# MCU_old.net
KiCad netlist of a schematic drawn in Altium Designer
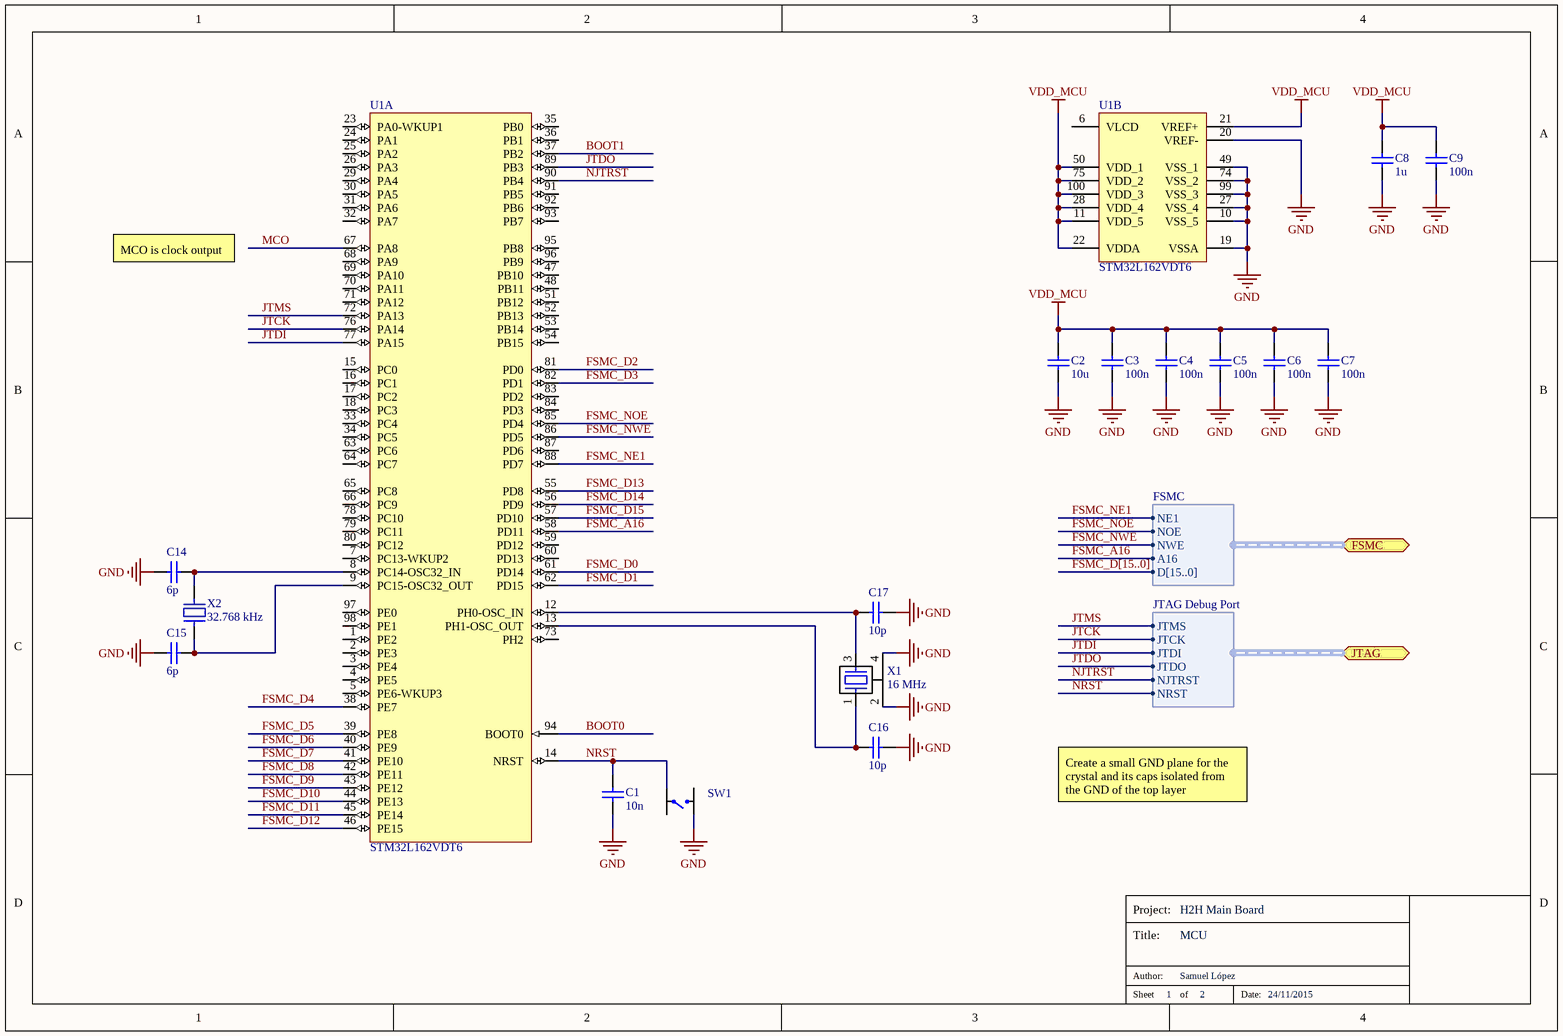
[diagram p0: MCU_old.SchDoc]

(export (version "E")
  (design (tool "Eeschema 10.0.6"))
  (components
    (comp (ref "C1")
      (value "10n")
      (footprint "C0603")
      (description "Capacitor")
      (libsource (lib "Common Devices") (part "Capacitor"))
    )
    (comp (ref "C2")
      (value "10u")
      (footprint "C0603")
      (description "Capacitor")
      (libsource (lib "Common Devices") (part "Capacitor"))
    )
    (comp (ref "C3")
      (value "100n")
      (footprint "C0603")
      (description "Capacitor")
      (libsource (lib "Common Devices") (part "Capacitor"))
    )
    (comp (ref "C4")
      (value "100n")
      (footprint "C0603")
      (description "Capacitor")
      (libsource (lib "Common Devices") (part "Capacitor"))
    )
    (comp (ref "C5")
      (value "100n")
      (footprint "C0603")
      (description "Capacitor")
      (libsource (lib "Common Devices") (part "Capacitor"))
    )
    (comp (ref "C6")
      (value "100n")
      (footprint "C0603")
      (description "Capacitor")
      (libsource (lib "Common Devices") (part "Capacitor"))
    )
    (comp (ref "C7")
      (value "100n")
      (footprint "C0603")
      (description "Capacitor")
      (libsource (lib "Common Devices") (part "Capacitor"))
    )
    (comp (ref "C8")
      (value "1u")
      (footprint "C0603")
      (description "Capacitor")
      (libsource (lib "Common Devices") (part "Capacitor"))
    )
    (comp (ref "C9")
      (value "100n")
      (footprint "C0603")
      (description "Capacitor")
      (libsource (lib "Common Devices") (part "Capacitor"))
    )
    (comp (ref "C14")
      (value "6p")
      (footprint "C0603")
      (description "Capacitor")
      (libsource (lib "Common Devices") (part "Capacitor"))
    )
    (comp (ref "C15")
      (value "6p")
      (footprint "C0603")
      (description "Capacitor")
      (libsource (lib "Common Devices") (part "Capacitor"))
    )
    (comp (ref "C16")
      (value "10p")
      (footprint "C0603")
      (description "Capacitor")
      (libsource (lib "Common Devices") (part "Capacitor"))
    )
    (comp (ref "C17")
      (value "10p")
      (footprint "C0603")
      (description "Capacitor")
      (libsource (lib "Common Devices") (part "Capacitor"))
    )
    (comp (ref "SW1")
      (value "EVQ-Q2K01W")
      (footprint "EVQ-Q2K01W")
      (description "Switch - SPST Off-Mom")
      (libsource (lib "Common Devices") (part "EVQ-Q2K01W"))
    )
    (comp (ref "U1")
      (value "STM32L162VDT6")
      (footprint "STM-LQFP100_N")
      (fields (field (name "MANUFACTURER") "STMicroelectronics"))
      (libsource (lib "STMicroelectronics STM32 L1") (part "STM32L162VDT6"))
    )
    (comp (ref "X1")
      (value "ABM3B-16.000MHZ-10-1-U")
      (footprint "ABM3B-16.000MHZ-10-1-U")
      (description "Crystal - 16 MHz")
      (fields (field (name "FREQUENCY") "16 MHz"))
      (libsource (lib "Main Board") (part "ABM3B-16.000MHZ-10-1-U"))
    )
    (comp (ref "X2")
      (value "ABS07-120-32.768KHZ-T")
      (footprint "ABS07-120-32.768KHZ-T")
      (description "Crystal - 32.768 kHz")
      (fields (field (name "FREQUENCY") "32.768 kHz"))
      (libsource (lib "Main Board") (part "ABS07-120-32.768KHZ-T"))
    )
  )
  (nets
    (net (code "5") (name "/BOOT0") (class "Default")
      (node (ref "U1") (pin "94") (pinfunction "BOOT0_94") (pintype "input"))
    )
    (net (code "6") (name "/BOOT1") (class "Default")
      (node (ref "U1") (pin "37") (pinfunction "PB2_37") (pintype "bidirectional"))
    )
    (net (code "7") (name "/FSMC_A16") (class "Default")
      (node (ref "U1") (pin "58") (pinfunction "PD11_58") (pintype "bidirectional"))
    )
    (net (code "8") (name "/FSMC_D0") (class "Default")
      (node (ref "U1") (pin "61") (pinfunction "PD14_61") (pintype "bidirectional"))
    )
    (net (code "9") (name "/FSMC_D1") (class "Default")
      (node (ref "U1") (pin "62") (pinfunction "PD15_62") (pintype "bidirectional"))
    )
    (net (code "10") (name "/FSMC_D2") (class "Default")
      (node (ref "U1") (pin "81") (pinfunction "PD0_81") (pintype "bidirectional"))
    )
    (net (code "11") (name "/FSMC_D3") (class "Default")
      (node (ref "U1") (pin "82") (pinfunction "PD1_82") (pintype "bidirectional"))
    )
    (net (code "12") (name "/FSMC_D4") (class "Default")
      (node (ref "U1") (pin "38") (pinfunction "PE7_38") (pintype "bidirectional"))
    )
    (net (code "13") (name "/FSMC_D5") (class "Default")
      (node (ref "U1") (pin "39") (pinfunction "PE8_39") (pintype "bidirectional"))
    )
    (net (code "14") (name "/FSMC_D6") (class "Default")
      (node (ref "U1") (pin "40") (pinfunction "PE9_40") (pintype "bidirectional"))
    )
    (net (code "15") (name "/FSMC_D7") (class "Default")
      (node (ref "U1") (pin "41") (pinfunction "PE10_41") (pintype "bidirectional"))
    )
    (net (code "16") (name "/FSMC_D8") (class "Default")
      (node (ref "U1") (pin "42") (pinfunction "PE11_42") (pintype "bidirectional"))
    )
    (net (code "17") (name "/FSMC_D9") (class "Default")
      (node (ref "U1") (pin "43") (pinfunction "PE12_43") (pintype "bidirectional"))
    )
    (net (code "18") (name "/FSMC_D10") (class "Default")
      (node (ref "U1") (pin "44") (pinfunction "PE13_44") (pintype "bidirectional"))
    )
    (net (code "19") (name "/FSMC_D11") (class "Default")
      (node (ref "U1") (pin "45") (pinfunction "PE14_45") (pintype "bidirectional"))
    )
    (net (code "20") (name "/FSMC_D12") (class "Default")
      (node (ref "U1") (pin "46") (pinfunction "PE15_46") (pintype "bidirectional"))
    )
    (net (code "21") (name "/FSMC_D13") (class "Default")
      (node (ref "U1") (pin "55") (pinfunction "PD8_55") (pintype "bidirectional"))
    )
    (net (code "22") (name "/FSMC_D14") (class "Default")
      (node (ref "U1") (pin "56") (pinfunction "PD9_56") (pintype "bidirectional"))
    )
    (net (code "23") (name "/FSMC_D15") (class "Default")
      (node (ref "U1") (pin "57") (pinfunction "PD10_57") (pintype "bidirectional"))
    )
    (net (code "25") (name "/FSMC_NE1") (class "Default")
      (node (ref "U1") (pin "88") (pinfunction "PD7_88") (pintype "bidirectional"))
    )
    (net (code "26") (name "/FSMC_NOE") (class "Default")
      (node (ref "U1") (pin "85") (pinfunction "PD4_85") (pintype "bidirectional"))
    )
    (net (code "27") (name "/FSMC_NWE") (class "Default")
      (node (ref "U1") (pin "86") (pinfunction "PD5_86") (pintype "bidirectional"))
    )
    (net (code "28") (name "/JTCK") (class "Default")
      (node (ref "U1") (pin "76") (pinfunction "PA14_76") (pintype "bidirectional"))
    )
    (net (code "29") (name "/JTDI") (class "Default")
      (node (ref "U1") (pin "77") (pinfunction "PA15_77") (pintype "bidirectional"))
    )
    (net (code "30") (name "/JTDO") (class "Default")
      (node (ref "U1") (pin "89") (pinfunction "PB3_89") (pintype "bidirectional"))
    )
    (net (code "31") (name "/JTMS") (class "Default")
      (node (ref "U1") (pin "72") (pinfunction "PA13_72") (pintype "bidirectional"))
    )
    (net (code "32") (name "/MCO") (class "Default")
      (node (ref "U1") (pin "67") (pinfunction "PA8_67") (pintype "bidirectional"))
    )
    (net (code "33") (name "/NJTRST") (class "Default")
      (node (ref "U1") (pin "90") (pinfunction "PB4_90") (pintype "bidirectional"))
    )
    (net (code "34") (name "/NRST") (class "Default")
      (node (ref "C1") (pin "2") (pinfunction "2_2") (pintype "passive"))
      (node (ref "SW1") (pin "1") (pinfunction "A1_1") (pintype "passive"))
      (node (ref "U1") (pin "14") (pinfunction "NRST_14") (pintype "bidirectional"))
    )
    (net (code "37") (name "GND") (class "Default")
      (node (ref "C1") (pin "1") (pinfunction "1_1") (pintype "passive"))
      (node (ref "C14") (pin "1") (pinfunction "1_1") (pintype "passive"))
      (node (ref "C15") (pin "1") (pinfunction "1_1") (pintype "passive"))
      (node (ref "C16") (pin "1") (pinfunction "1_1") (pintype "passive"))
      (node (ref "C17") (pin "1") (pinfunction "1_1") (pintype "passive"))
      (node (ref "C2") (pin "1") (pinfunction "1_1") (pintype "passive"))
      (node (ref "C3") (pin "1") (pinfunction "1_1") (pintype "passive"))
      (node (ref "C4") (pin "1") (pinfunction "1_1") (pintype "passive"))
      (node (ref "C5") (pin "1") (pinfunction "1_1") (pintype "passive"))
      (node (ref "C6") (pin "1") (pinfunction "1_1") (pintype "passive"))
      (node (ref "C7") (pin "1") (pinfunction "1_1") (pintype "passive"))
      (node (ref "C8") (pin "1") (pinfunction "1_1") (pintype "passive"))
      (node (ref "C9") (pin "1") (pinfunction "1_1") (pintype "passive"))
      (node (ref "SW1") (pin "3") (pinfunction "B2_3") (pintype "passive"))
      (node (ref "U1") (pin "10") (pinfunction "VSS_5_10") (pintype "power_in"))
      (node (ref "U1") (pin "19") (pinfunction "VSSA_19") (pintype "power_in"))
      (node (ref "U1") (pin "20") (pinfunction "VREF-_20") (pintype "power_in"))
      (node (ref "U1") (pin "27") (pinfunction "VSS_4_27") (pintype "power_in"))
      (node (ref "U1") (pin "49") (pinfunction "VSS_1_49") (pintype "power_in"))
      (node (ref "U1") (pin "74") (pinfunction "VSS_2_74") (pintype "power_in"))
      (node (ref "U1") (pin "99") (pinfunction "VSS_3_99") (pintype "power_in"))
      (node (ref "X1") (pin "2") (pinfunction "2_2") (pintype "passive"))
      (node (ref "X1") (pin "4") (pinfunction "4_4") (pintype "passive"))
    )
    (net (code "38") (name "Net-(U1A-PC14-OSC32_IN)") (class "Default")
      (node (ref "C14") (pin "2") (pinfunction "2_2") (pintype "passive"))
      (node (ref "U1") (pin "8") (pinfunction "PC14-OSC32_IN_8") (pintype "bidirectional"))
      (node (ref "X2") (pin "1") (pinfunction "1_1") (pintype "passive"))
    )
    (net (code "39") (name "Net-(U1A-PC15-OSC32_OUT)") (class "Default")
      (node (ref "C15") (pin "2") (pinfunction "2_2") (pintype "passive"))
      (node (ref "U1") (pin "9") (pinfunction "PC15-OSC32_OUT_9") (pintype "bidirectional"))
      (node (ref "X2") (pin "2") (pinfunction "2_2") (pintype "passive"))
    )
    (net (code "40") (name "Net-(U1A-PH0-OSC_IN)") (class "Default")
      (node (ref "C17") (pin "2") (pinfunction "2_2") (pintype "passive"))
      (node (ref "U1") (pin "12") (pinfunction "PH0-OSC_IN_12") (pintype "bidirectional"))
      (node (ref "X1") (pin "3") (pinfunction "3_3") (pintype "passive"))
    )
    (net (code "41") (name "Net-(U1A-PH1-OSC_OUT)") (class "Default")
      (node (ref "C16") (pin "2") (pinfunction "2_2") (pintype "passive"))
      (node (ref "U1") (pin "13") (pinfunction "PH1-OSC_OUT_13") (pintype "bidirectional"))
      (node (ref "X1") (pin "1") (pinfunction "1_1") (pintype "passive"))
    )
    (net (code "42") (name "VDD_MCU") (class "Default")
      (node (ref "C2") (pin "2") (pinfunction "2_2") (pintype "passive"))
      (node (ref "C3") (pin "2") (pinfunction "2_2") (pintype "passive"))
      (node (ref "C4") (pin "2") (pinfunction "2_2") (pintype "passive"))
      (node (ref "C5") (pin "2") (pinfunction "2_2") (pintype "passive"))
      (node (ref "C6") (pin "2") (pinfunction "2_2") (pintype "passive"))
      (node (ref "C7") (pin "2") (pinfunction "2_2") (pintype "passive"))
      (node (ref "C8") (pin "2") (pinfunction "2_2") (pintype "passive"))
      (node (ref "C9") (pin "2") (pinfunction "2_2") (pintype "passive"))
      (node (ref "U1") (pin "100") (pinfunction "VDD_3_100") (pintype "power_in"))
      (node (ref "U1") (pin "11") (pinfunction "VDD_5_11") (pintype "power_in"))
      (node (ref "U1") (pin "21") (pinfunction "VREF+_21") (pintype "power_in"))
      (node (ref "U1") (pin "22") (pinfunction "VDDA_22") (pintype "power_in"))
      (node (ref "U1") (pin "28") (pinfunction "VDD_4_28") (pintype "power_in"))
      (node (ref "U1") (pin "50") (pinfunction "VDD_1_50") (pintype "power_in"))
      (node (ref "U1") (pin "75") (pinfunction "VDD_2_75") (pintype "power_in"))
    )
    (net (code "43") (name "unconnected-(SW1-A2-Pad2)") (class "Default")
      (node (ref "SW1") (pin "2") (pinfunction "A2_2") (pintype "passive"))
    )
    (net (code "44") (name "unconnected-(SW1-B1-Pad4)") (class "Default")
      (node (ref "SW1") (pin "4") (pinfunction "B1_4") (pintype "passive"))
    )
    (net (code "45") (name "unconnected-(U1A-PA0-WKUP1-Pad23)") (class "Default")
      (node (ref "U1") (pin "23") (pinfunction "PA0-WKUP1_23") (pintype "bidirectional"))
    )
    (net (code "46") (name "unconnected-(U1A-PA1-Pad24)") (class "Default")
      (node (ref "U1") (pin "24") (pinfunction "PA1_24") (pintype "bidirectional"))
    )
    (net (code "47") (name "unconnected-(U1A-PA2-Pad25)") (class "Default")
      (node (ref "U1") (pin "25") (pinfunction "PA2_25") (pintype "bidirectional"))
    )
    (net (code "48") (name "unconnected-(U1A-PA3-Pad26)") (class "Default")
      (node (ref "U1") (pin "26") (pinfunction "PA3_26") (pintype "bidirectional"))
    )
    (net (code "49") (name "unconnected-(U1A-PA4-Pad29)") (class "Default")
      (node (ref "U1") (pin "29") (pinfunction "PA4_29") (pintype "bidirectional"))
    )
    (net (code "50") (name "unconnected-(U1A-PA5-Pad30)") (class "Default")
      (node (ref "U1") (pin "30") (pinfunction "PA5_30") (pintype "bidirectional"))
    )
    (net (code "51") (name "unconnected-(U1A-PA6-Pad31)") (class "Default")
      (node (ref "U1") (pin "31") (pinfunction "PA6_31") (pintype "bidirectional"))
    )
    (net (code "52") (name "unconnected-(U1A-PA7-Pad32)") (class "Default")
      (node (ref "U1") (pin "32") (pinfunction "PA7_32") (pintype "bidirectional"))
    )
    (net (code "53") (name "unconnected-(U1A-PA9-Pad68)") (class "Default")
      (node (ref "U1") (pin "68") (pinfunction "PA9_68") (pintype "bidirectional"))
    )
    (net (code "54") (name "unconnected-(U1A-PA10-Pad69)") (class "Default")
      (node (ref "U1") (pin "69") (pinfunction "PA10_69") (pintype "bidirectional"))
    )
    (net (code "55") (name "unconnected-(U1A-PA11-Pad70)") (class "Default")
      (node (ref "U1") (pin "70") (pinfunction "PA11_70") (pintype "bidirectional"))
    )
    (net (code "56") (name "unconnected-(U1A-PA12-Pad71)") (class "Default")
      (node (ref "U1") (pin "71") (pinfunction "PA12_71") (pintype "bidirectional"))
    )
    (net (code "57") (name "unconnected-(U1A-PB0-Pad35)") (class "Default")
      (node (ref "U1") (pin "35") (pinfunction "PB0_35") (pintype "bidirectional"))
    )
    (net (code "58") (name "unconnected-(U1A-PB1-Pad36)") (class "Default")
      (node (ref "U1") (pin "36") (pinfunction "PB1_36") (pintype "bidirectional"))
    )
    (net (code "59") (name "unconnected-(U1A-PB5-Pad91)") (class "Default")
      (node (ref "U1") (pin "91") (pinfunction "PB5_91") (pintype "bidirectional"))
    )
    (net (code "60") (name "unconnected-(U1A-PB6-Pad92)") (class "Default")
      (node (ref "U1") (pin "92") (pinfunction "PB6_92") (pintype "bidirectional"))
    )
    (net (code "61") (name "unconnected-(U1A-PB7-Pad93)") (class "Default")
      (node (ref "U1") (pin "93") (pinfunction "PB7_93") (pintype "bidirectional"))
    )
    (net (code "62") (name "unconnected-(U1A-PB8-Pad95)") (class "Default")
      (node (ref "U1") (pin "95") (pinfunction "PB8_95") (pintype "bidirectional"))
    )
    (net (code "63") (name "unconnected-(U1A-PB9-Pad96)") (class "Default")
      (node (ref "U1") (pin "96") (pinfunction "PB9_96") (pintype "bidirectional"))
    )
    (net (code "64") (name "unconnected-(U1A-PB10-Pad47)") (class "Default")
      (node (ref "U1") (pin "47") (pinfunction "PB10_47") (pintype "bidirectional"))
    )
    (net (code "65") (name "unconnected-(U1A-PB11-Pad48)") (class "Default")
      (node (ref "U1") (pin "48") (pinfunction "PB11_48") (pintype "bidirectional"))
    )
    (net (code "66") (name "unconnected-(U1A-PB12-Pad51)") (class "Default")
      (node (ref "U1") (pin "51") (pinfunction "PB12_51") (pintype "bidirectional"))
    )
    (net (code "67") (name "unconnected-(U1A-PB13-Pad52)") (class "Default")
      (node (ref "U1") (pin "52") (pinfunction "PB13_52") (pintype "bidirectional"))
    )
    (net (code "68") (name "unconnected-(U1A-PB14-Pad53)") (class "Default")
      (node (ref "U1") (pin "53") (pinfunction "PB14_53") (pintype "bidirectional"))
    )
    (net (code "69") (name "unconnected-(U1A-PB15-Pad54)") (class "Default")
      (node (ref "U1") (pin "54") (pinfunction "PB15_54") (pintype "bidirectional"))
    )
    (net (code "70") (name "unconnected-(U1A-PC0-Pad15)") (class "Default")
      (node (ref "U1") (pin "15") (pinfunction "PC0_15") (pintype "bidirectional"))
    )
    (net (code "71") (name "unconnected-(U1A-PC1-Pad16)") (class "Default")
      (node (ref "U1") (pin "16") (pinfunction "PC1_16") (pintype "bidirectional"))
    )
    (net (code "72") (name "unconnected-(U1A-PC2-Pad17)") (class "Default")
      (node (ref "U1") (pin "17") (pinfunction "PC2_17") (pintype "bidirectional"))
    )
    (net (code "73") (name "unconnected-(U1A-PC3-Pad18)") (class "Default")
      (node (ref "U1") (pin "18") (pinfunction "PC3_18") (pintype "bidirectional"))
    )
    (net (code "74") (name "unconnected-(U1A-PC4-Pad33)") (class "Default")
      (node (ref "U1") (pin "33") (pinfunction "PC4_33") (pintype "bidirectional"))
    )
    (net (code "75") (name "unconnected-(U1A-PC5-Pad34)") (class "Default")
      (node (ref "U1") (pin "34") (pinfunction "PC5_34") (pintype "bidirectional"))
    )
    (net (code "76") (name "unconnected-(U1A-PC6-Pad63)") (class "Default")
      (node (ref "U1") (pin "63") (pinfunction "PC6_63") (pintype "bidirectional"))
    )
    (net (code "77") (name "unconnected-(U1A-PC7-Pad64)") (class "Default")
      (node (ref "U1") (pin "64") (pinfunction "PC7_64") (pintype "bidirectional"))
    )
    (net (code "78") (name "unconnected-(U1A-PC8-Pad65)") (class "Default")
      (node (ref "U1") (pin "65") (pinfunction "PC8_65") (pintype "bidirectional"))
    )
    (net (code "79") (name "unconnected-(U1A-PC9-Pad66)") (class "Default")
      (node (ref "U1") (pin "66") (pinfunction "PC9_66") (pintype "bidirectional"))
    )
    (net (code "80") (name "unconnected-(U1A-PC10-Pad78)") (class "Default")
      (node (ref "U1") (pin "78") (pinfunction "PC10_78") (pintype "bidirectional"))
    )
    (net (code "81") (name "unconnected-(U1A-PC11-Pad79)") (class "Default")
      (node (ref "U1") (pin "79") (pinfunction "PC11_79") (pintype "bidirectional"))
    )
    (net (code "82") (name "unconnected-(U1A-PC12-Pad80)") (class "Default")
      (node (ref "U1") (pin "80") (pinfunction "PC12_80") (pintype "bidirectional"))
    )
    (net (code "83") (name "unconnected-(U1A-PC13-WKUP2-Pad7)") (class "Default")
      (node (ref "U1") (pin "7") (pinfunction "PC13-WKUP2_7") (pintype "bidirectional"))
    )
    (net (code "84") (name "unconnected-(U1A-PD2-Pad83)") (class "Default")
      (node (ref "U1") (pin "83") (pinfunction "PD2_83") (pintype "bidirectional"))
    )
    (net (code "85") (name "unconnected-(U1A-PD3-Pad84)") (class "Default")
      (node (ref "U1") (pin "84") (pinfunction "PD3_84") (pintype "bidirectional"))
    )
    (net (code "86") (name "unconnected-(U1A-PD6-Pad87)") (class "Default")
      (node (ref "U1") (pin "87") (pinfunction "PD6_87") (pintype "bidirectional"))
    )
    (net (code "87") (name "unconnected-(U1A-PD12-Pad59)") (class "Default")
      (node (ref "U1") (pin "59") (pinfunction "PD12_59") (pintype "bidirectional"))
    )
    (net (code "88") (name "unconnected-(U1A-PD13-Pad60)") (class "Default")
      (node (ref "U1") (pin "60") (pinfunction "PD13_60") (pintype "bidirectional"))
    )
    (net (code "89") (name "unconnected-(U1A-PE0-Pad97)") (class "Default")
      (node (ref "U1") (pin "97") (pinfunction "PE0_97") (pintype "bidirectional"))
    )
    (net (code "90") (name "unconnected-(U1A-PE1-Pad98)") (class "Default")
      (node (ref "U1") (pin "98") (pinfunction "PE1_98") (pintype "bidirectional"))
    )
    (net (code "91") (name "unconnected-(U1A-PE2-Pad1)") (class "Default")
      (node (ref "U1") (pin "1") (pinfunction "PE2_1") (pintype "bidirectional"))
    )
    (net (code "92") (name "unconnected-(U1A-PE3-Pad2)") (class "Default")
      (node (ref "U1") (pin "2") (pinfunction "PE3_2") (pintype "bidirectional"))
    )
    (net (code "93") (name "unconnected-(U1A-PE4-Pad3)") (class "Default")
      (node (ref "U1") (pin "3") (pinfunction "PE4_3") (pintype "bidirectional"))
    )
    (net (code "94") (name "unconnected-(U1A-PE5-Pad4)") (class "Default")
      (node (ref "U1") (pin "4") (pinfunction "PE5_4") (pintype "bidirectional"))
    )
    (net (code "95") (name "unconnected-(U1A-PE6-WKUP3-Pad5)") (class "Default")
      (node (ref "U1") (pin "5") (pinfunction "PE6-WKUP3_5") (pintype "bidirectional"))
    )
    (net (code "96") (name "unconnected-(U1A-PH2-Pad73)") (class "Default")
      (node (ref "U1") (pin "73") (pinfunction "PH2_73") (pintype "bidirectional"))
    )
    (net (code "97") (name "unconnected-(U1B-VLCD-Pad6)") (class "Default")
      (node (ref "U1") (pin "6") (pinfunction "VLCD_6") (pintype "power_in"))
    )
  )
)
